# Atmega328.net
KiCad netlist of a schematic drawn in Altium Designer
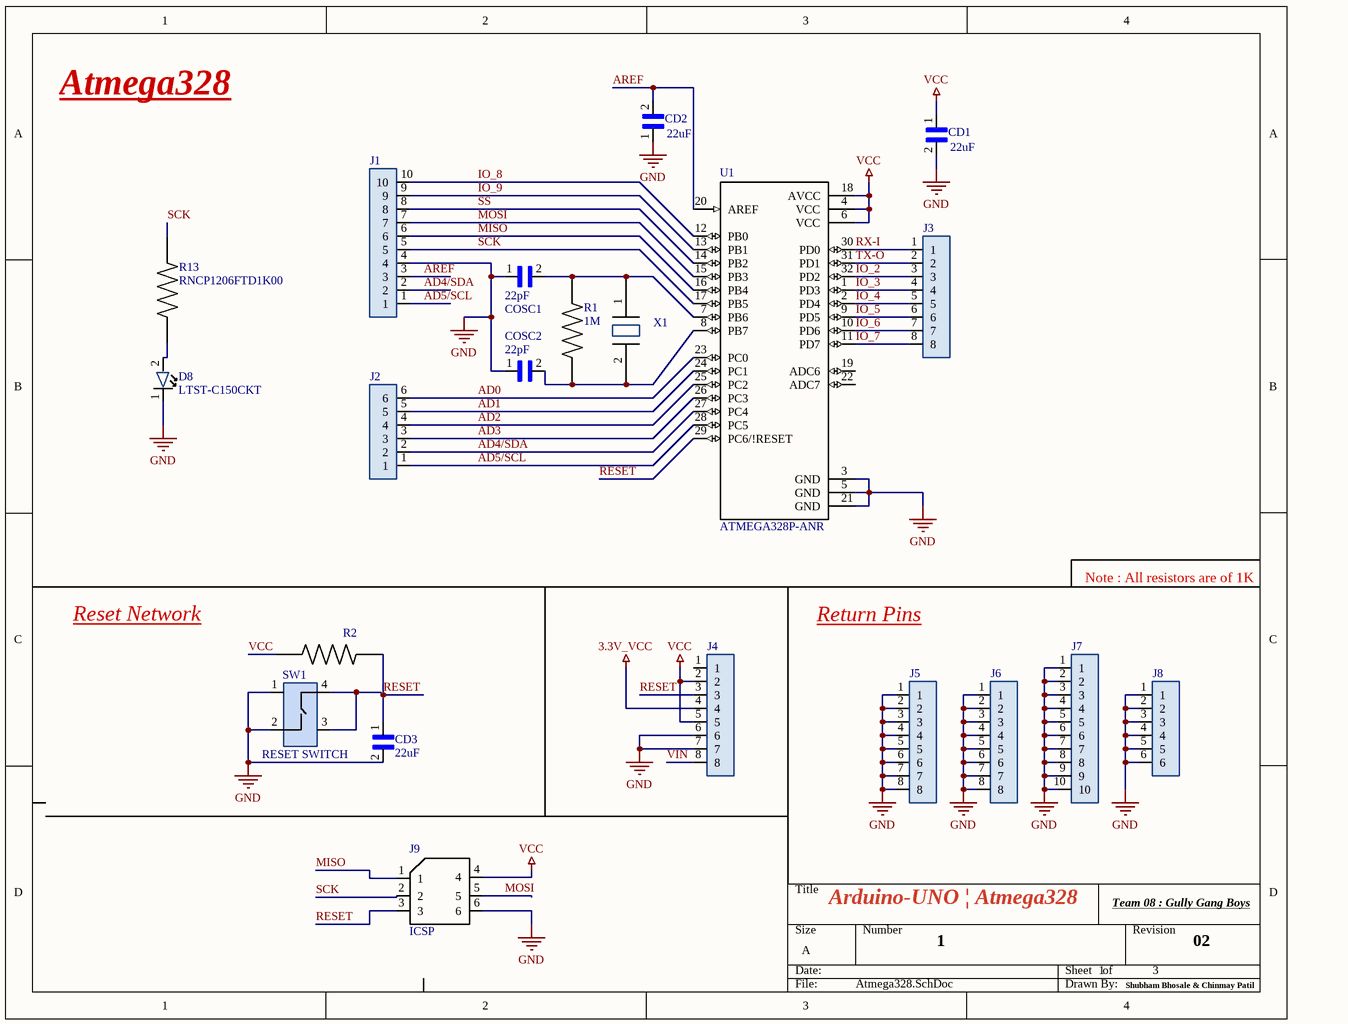
[diagram p0: Atmega328.SchDoc]

(export (version "E")
  (design (tool "Eeschema 10.0.6"))
  (components
    (comp (ref "CD1")
      (value "22uF")
      (footprint "1206_Passive")
      (description "22µF ±20% 16V Ceramic Capacitor X5R 1206 (3216 Metric)")
      (fields (field (name "DIGIKEY PART") "1276-2728-1-ND"))
      (libsource (lib "brd2_rev2") (part "1206_22uF"))
    )
    (comp (ref "CD2")
      (value "22uF")
      (footprint "1206_Passive")
      (description "22µF ±20% 16V Ceramic Capacitor X5R 1206 (3216 Metric)")
      (fields (field (name "DIGIKEY PART") "1276-2728-1-ND"))
      (libsource (lib "brd2_rev2") (part "1206_22uF"))
    )
    (comp (ref "CD3")
      (value "22uF")
      (footprint "1206_Passive")
      (description "22µF ±20% 16V Ceramic Capacitor X5R 1206 (3216 Metric)")
      (fields (field (name "DIGIKEY PART") "1276-2728-1-ND"))
      (libsource (lib "brd2_rev2") (part "1206_22uF"))
    )
    (comp (ref "COSC1")
      (value "22pF")
      (footprint "1206_Passive")
      (description "22pF ±5% 16V Ceramic Capacitor C0G, NP0 1206 (3216 Metric)")
      (fields (field (name "DIGIKEY PART") "732-7867-1-ND"))
      (libsource (lib "brd2_rev2") (part "1206_22pF"))
    )
    (comp (ref "COSC2")
      (value "22pF")
      (footprint "1206_Passive")
      (description "22pF ±5% 16V Ceramic Capacitor C0G, NP0 1206 (3216 Metric)")
      (fields (field (name "DIGIKEY PART") "732-7867-1-ND"))
      (libsource (lib "brd2_rev2") (part "1206_22pF"))
    )
    (comp (ref "D8")
      (value "LTST-C150CKT")
      (footprint "LED")
      (description "Red 638nm LED Indication - Discrete 1.8V 1206 (3216 Metric)")
      (fields (field (name "DIGIKEY PART") "160-1167-1-ND"))
      (libsource (lib "brd2_rev2") (part "1206_RED_LED"))
    )
    (comp (ref "J1")
      (value "PPTC101LFBN-RC")
      (footprint "10_PIN")
      (description "10 Position Header Connector 0.100\" (2.54mm) Through Hole Tin")
      (fields (field (name "DIGIKEY PART") "S7008-ND"))
      (libsource (lib "") (part "10_PIN_FEMALE_1"))
    )
    (comp (ref "J2")
      (value "PPTC061LFBN-RC")
      (footprint "6_PIN")
      (description "6 Position Header Connector 0.100\" (2.54mm) Through Hole Tin")
      (fields (field (name "DIGIKEY PART") "S7004-ND"))
      (libsource (lib "brd2_rev2") (part "6_PIN_FEMALE"))
    )
    (comp (ref "J3")
      (value "PPTC081LFBN-RC")
      (footprint "8_PIN")
      (description "8 Position Header Connector 0.100\" (2.54mm) Through Hole Tin")
      (fields (field (name "DIGIKEY PART") "S7006-ND"))
      (libsource (lib "brd2_rev2") (part "8_PIN_FEMALE"))
    )
    (comp (ref "J4")
      (value "PPTC081LFBN-RC")
      (footprint "8_PIN")
      (description "8 Position Header Connector 0.100\" (2.54mm) Through Hole Tin")
      (fields (field (name "DIGIKEY PART") "S7006-ND"))
      (libsource (lib "brd2_rev2") (part "8_PIN_FEMALE"))
    )
    (comp (ref "J5")
      (value "PPTC081LFBN-RC")
      (footprint "8_PIN")
      (description "8 Position Header Connector 0.100\" (2.54mm) Through Hole Tin")
      (fields (field (name "DIGIKEY PART") "S7006-ND"))
      (libsource (lib "brd2_rev2") (part "8_PIN_FEMALE"))
    )
    (comp (ref "J6")
      (value "PPTC081LFBN-RC")
      (footprint "8_PIN")
      (description "8 Position Header Connector 0.100\" (2.54mm) Through Hole Tin")
      (fields (field (name "DIGIKEY PART") "S7006-ND"))
      (libsource (lib "brd2_rev2") (part "8_PIN_FEMALE"))
    )
    (comp (ref "J7")
      (value "PPTC101LFBN-RC")
      (footprint "10_PIN")
      (description "10 Position Header Connector 0.100\" (2.54mm) Through Hole Tin")
      (fields (field (name "DIGIKEY PART") "S7008-ND"))
      (libsource (lib "brd2_rev2") (part "10_PIN_FEMALE"))
    )
    (comp (ref "J8")
      (value "PPTC061LFBN-RC")
      (footprint "6_PIN")
      (description "6 Position Header Connector 0.100\" (2.54mm) Through Hole Tin")
      (fields (field (name "DIGIKEY PART") "S7004-ND"))
      (libsource (lib "") (part "6_PIN_FEMALE_1"))
    )
    (comp (ref "J9")
      (value "ICSP")
      (footprint "ICSP")
      (description "Connector Header Through Hole 6 position 0.079\" (2.00mm)")
      (fields (field (name "DIGIKEY PART") "S5801-03-ND"))
      (libsource (lib "brd2_rev2") (part "ICSP"))
    )
    (comp (ref "R1")
      (value "1M")
      (footprint "1206_Passive")
      (description "1 MOhms ±5% 0.25W, 1/4W Chip Resistor 1206 (3216 Metric) Automotive AEC-Q200 Thick Film")
      (fields (field (name "DIGIKEY PART") "Number RMCF1206JT1M00CT-ND"))
      (libsource (lib "brd2_rev2") (part "1206_1M"))
    )
    (comp (ref "R2")
      (value "RNCP1206FTD1K00")
      (footprint "1206_Passive")
      (description "1 kOhms ±1% 0.5W, 1/2W Chip Resistor 1206 (3216 Metric) Anti-Sulfur, Moisture Resistant Thin Film")
      (fields (field (name "DIGIKEY PART") "RNCP1206FTD1K00CT-ND"))
      (libsource (lib "brd2_rev2") (part "1206_1K"))
    )
    (comp (ref "R13")
      (value "RNCP1206FTD1K00")
      (footprint "1206_Passive")
      (description "1 kOhms ±1% 0.5W, 1/2W Chip Resistor 1206 (3216 Metric) Anti-Sulfur, Moisture Resistant Thin Film")
      (fields (field (name "DIGIKEY PART") "RNCP1206FTD1K00CT-ND"))
      (libsource (lib "brd2_rev2") (part "1206_1K"))
    )
    (comp (ref "SW1")
      (value "RESET SWITCH")
      (footprint "Switch")
      (description "Tactile Switch SPST-NO Top Actuated Surface Mount")
      (fields (field (name "DIGIKEY PART") "EG5350CT-ND"))
      (libsource (lib "brd2_rev2") (part "Push_Button"))
    )
    (comp (ref "U1")
      (value "ATMEGA328P-ANR")
      (footprint "ATMega328P")
      (description "AVR AVR® ATmega Microcontroller IC 8-Bit 20MHz 32KB (16K x 16) FLASH 32-TQFP (7x7)")
      (fields (field (name "DIGIKEY PART") "ATMEGA328P-ANRCT-ND"))
      (libsource (lib "brd2_rev2") (part "ATMega328P"))
    )
    (comp (ref "X1")
      (value "ABLS-16.000MHZ-B4-T")
      (footprint "Crystal")
      (description "16MHz ±30ppm Crystal 18pF 40 Ohms HC-49/US")
      (fields (field (name "DIGIKEY PART") "535-10226-1-ND"))
      (libsource (lib "brd2_rev2") (part "16MHz_Crystal"))
    )
  )
  (nets
    (net (code "1") (name "/AD0") (class "Default")
      (node (ref "J2") (pin "6") (pinfunction "6_6") (pintype "passive"))
      (node (ref "U1") (pin "23") (pinfunction "PC0_23") (pintype "bidirectional"))
    )
    (net (code "2") (name "/AD1") (class "Default")
      (node (ref "J2") (pin "5") (pinfunction "5_5") (pintype "passive"))
      (node (ref "U1") (pin "24") (pinfunction "PC1_24") (pintype "bidirectional"))
    )
    (net (code "3") (name "/AD2") (class "Default")
      (node (ref "J2") (pin "4") (pinfunction "4_4") (pintype "passive"))
      (node (ref "U1") (pin "25") (pinfunction "PC2_25") (pintype "bidirectional"))
    )
    (net (code "4") (name "/AD3") (class "Default")
      (node (ref "J2") (pin "3") (pinfunction "3_3") (pintype "passive"))
      (node (ref "U1") (pin "26") (pinfunction "PC3_26") (pintype "bidirectional"))
    )
    (net (code "5") (name "/AD4{slash}SDA") (class "Default")
      (node (ref "J1") (pin "2") (pinfunction "2_2") (pintype "passive"))
      (node (ref "J2") (pin "2") (pinfunction "2_2") (pintype "passive"))
      (node (ref "U1") (pin "27") (pinfunction "PC4_27") (pintype "bidirectional"))
    )
    (net (code "6") (name "/AD5{slash}SCL") (class "Default")
      (node (ref "J1") (pin "1") (pinfunction "1_1") (pintype "passive"))
      (node (ref "J2") (pin "1") (pinfunction "1_1") (pintype "passive"))
      (node (ref "U1") (pin "28") (pinfunction "PC5_28") (pintype "bidirectional"))
    )
    (net (code "7") (name "/AREF") (class "Default")
      (node (ref "CD2") (pin "2") (pinfunction "2_2") (pintype "passive"))
      (node (ref "J1") (pin "3") (pinfunction "3_3") (pintype "passive"))
      (node (ref "U1") (pin "20") (pinfunction "AREF_20") (pintype "input"))
    )
    (net (code "8") (name "/IO_2") (class "Default")
      (node (ref "J3") (pin "3") (pinfunction "3_3") (pintype "passive"))
      (node (ref "U1") (pin "32") (pinfunction "PD2_32") (pintype "bidirectional"))
    )
    (net (code "9") (name "/IO_3") (class "Default")
      (node (ref "J3") (pin "4") (pinfunction "4_4") (pintype "passive"))
      (node (ref "U1") (pin "1") (pinfunction "PD3_1") (pintype "bidirectional"))
    )
    (net (code "10") (name "/IO_4") (class "Default")
      (node (ref "J3") (pin "5") (pinfunction "5_5") (pintype "passive"))
      (node (ref "U1") (pin "2") (pinfunction "PD4_2") (pintype "bidirectional"))
    )
    (net (code "11") (name "/IO_5") (class "Default")
      (node (ref "J3") (pin "6") (pinfunction "6_6") (pintype "passive"))
      (node (ref "U1") (pin "9") (pinfunction "PD5_9") (pintype "bidirectional"))
    )
    (net (code "12") (name "/IO_6") (class "Default")
      (node (ref "J3") (pin "7") (pinfunction "7_7") (pintype "passive"))
      (node (ref "U1") (pin "10") (pinfunction "PD6_10") (pintype "bidirectional"))
    )
    (net (code "13") (name "/IO_7") (class "Default")
      (node (ref "J3") (pin "8") (pinfunction "8_8") (pintype "passive"))
      (node (ref "U1") (pin "11") (pinfunction "PD7_11") (pintype "bidirectional"))
    )
    (net (code "14") (name "/IO_8") (class "Default")
      (node (ref "J1") (pin "10") (pinfunction "10_10") (pintype "passive"))
      (node (ref "U1") (pin "12") (pinfunction "PB0_12") (pintype "bidirectional"))
    )
    (net (code "15") (name "/IO_9") (class "Default")
      (node (ref "J1") (pin "9") (pinfunction "9_9") (pintype "passive"))
      (node (ref "U1") (pin "13") (pinfunction "PB1_13") (pintype "bidirectional"))
    )
    (net (code "16") (name "/MISO") (class "Default")
      (node (ref "J1") (pin "6") (pinfunction "6_6") (pintype "passive"))
      (node (ref "J9") (pin "1") (pinfunction "1_1") (pintype "passive"))
      (node (ref "U1") (pin "16") (pinfunction "PB4_16") (pintype "bidirectional"))
    )
    (net (code "17") (name "/MOSI") (class "Default")
      (node (ref "J1") (pin "7") (pinfunction "7_7") (pintype "passive"))
      (node (ref "J9") (pin "5") (pinfunction "5_5") (pintype "passive"))
      (node (ref "U1") (pin "15") (pinfunction "PB3_15") (pintype "bidirectional"))
    )
    (net (code "18") (name "/RESET") (class "Default")
      (node (ref "CD3") (pin "1") (pinfunction "1_1") (pintype "passive"))
      (node (ref "J4") (pin "3") (pinfunction "3_3") (pintype "passive"))
      (node (ref "J9") (pin "3") (pinfunction "3_3") (pintype "passive"))
      (node (ref "R2") (pin "2") (pinfunction "2_2") (pintype "passive"))
      (node (ref "SW1") (pin "3") (pinfunction "3_3") (pintype "passive"))
      (node (ref "SW1") (pin "4") (pinfunction "4_4") (pintype "passive"))
      (node (ref "U1") (pin "29") (pinfunction "PC6/!RESET_29") (pintype "bidirectional"))
    )
    (net (code "19") (name "/RX-I") (class "Default")
      (node (ref "J3") (pin "1") (pinfunction "1_1") (pintype "passive"))
      (node (ref "U1") (pin "30") (pinfunction "PD0_30") (pintype "bidirectional"))
    )
    (net (code "20") (name "/SCK") (class "Default")
      (node (ref "J1") (pin "5") (pinfunction "5_5") (pintype "passive"))
      (node (ref "J9") (pin "2") (pinfunction "2_2") (pintype "passive"))
      (node (ref "R13") (pin "2") (pinfunction "2_2") (pintype "passive"))
      (node (ref "U1") (pin "17") (pinfunction "PB5_17") (pintype "bidirectional"))
    )
    (net (code "21") (name "/SS") (class "Default")
      (node (ref "J1") (pin "8") (pinfunction "8_8") (pintype "passive"))
      (node (ref "U1") (pin "14") (pinfunction "PB2_14") (pintype "bidirectional"))
    )
    (net (code "22") (name "/TX-O") (class "Default")
      (node (ref "J3") (pin "2") (pinfunction "2_2") (pintype "passive"))
      (node (ref "U1") (pin "31") (pinfunction "PD1_31") (pintype "bidirectional"))
    )
    (net (code "23") (name "/VIN") (class "Default")
      (node (ref "J4") (pin "8") (pinfunction "8_8") (pintype "passive"))
    )
    (net (code "24") (name "3.3V_VCC") (class "Default")
      (node (ref "J4") (pin "4") (pinfunction "4_4") (pintype "passive"))
    )
    (net (code "25") (name "GND") (class "Default")
      (node (ref "CD1") (pin "2") (pinfunction "2_2") (pintype "passive"))
      (node (ref "CD2") (pin "1") (pinfunction "1_1") (pintype "passive"))
      (node (ref "CD3") (pin "2") (pinfunction "2_2") (pintype "passive"))
      (node (ref "COSC1") (pin "1") (pinfunction "1_1") (pintype "passive"))
      (node (ref "COSC2") (pin "1") (pinfunction "1_1") (pintype "passive"))
      (node (ref "D8") (pin "1") (pinfunction "1_1") (pintype "passive"))
      (node (ref "J1") (pin "4") (pinfunction "4_4") (pintype "passive"))
      (node (ref "J4") (pin "6") (pinfunction "6_6") (pintype "passive"))
      (node (ref "J4") (pin "7") (pinfunction "7_7") (pintype "passive"))
      (node (ref "J5") (pin "1") (pinfunction "1_1") (pintype "passive"))
      (node (ref "J5") (pin "2") (pinfunction "2_2") (pintype "passive"))
      (node (ref "J5") (pin "3") (pinfunction "3_3") (pintype "passive"))
      (node (ref "J5") (pin "4") (pinfunction "4_4") (pintype "passive"))
      (node (ref "J5") (pin "5") (pinfunction "5_5") (pintype "passive"))
      (node (ref "J5") (pin "6") (pinfunction "6_6") (pintype "passive"))
      (node (ref "J5") (pin "7") (pinfunction "7_7") (pintype "passive"))
      (node (ref "J5") (pin "8") (pinfunction "8_8") (pintype "passive"))
      (node (ref "J6") (pin "1") (pinfunction "1_1") (pintype "passive"))
      (node (ref "J6") (pin "2") (pinfunction "2_2") (pintype "passive"))
      (node (ref "J6") (pin "3") (pinfunction "3_3") (pintype "passive"))
      (node (ref "J6") (pin "4") (pinfunction "4_4") (pintype "passive"))
      (node (ref "J6") (pin "5") (pinfunction "5_5") (pintype "passive"))
      (node (ref "J6") (pin "6") (pinfunction "6_6") (pintype "passive"))
      (node (ref "J6") (pin "7") (pinfunction "7_7") (pintype "passive"))
      (node (ref "J6") (pin "8") (pinfunction "8_8") (pintype "passive"))
      (node (ref "J7") (pin "1") (pinfunction "1_1") (pintype "passive"))
      (node (ref "J7") (pin "10") (pinfunction "10_10") (pintype "passive"))
      (node (ref "J7") (pin "2") (pinfunction "2_2") (pintype "passive"))
      (node (ref "J7") (pin "3") (pinfunction "3_3") (pintype "passive"))
      (node (ref "J7") (pin "4") (pinfunction "4_4") (pintype "passive"))
      (node (ref "J7") (pin "5") (pinfunction "5_5") (pintype "passive"))
      (node (ref "J7") (pin "6") (pinfunction "6_6") (pintype "passive"))
      (node (ref "J7") (pin "7") (pinfunction "7_7") (pintype "passive"))
      (node (ref "J7") (pin "8") (pinfunction "8_8") (pintype "passive"))
      (node (ref "J7") (pin "9") (pinfunction "9_9") (pintype "passive"))
      (node (ref "J8") (pin "1") (pinfunction "1_1") (pintype "passive"))
      (node (ref "J8") (pin "2") (pinfunction "2_2") (pintype "passive"))
      (node (ref "J8") (pin "3") (pinfunction "3_3") (pintype "passive"))
      (node (ref "J8") (pin "4") (pinfunction "4_4") (pintype "passive"))
      (node (ref "J8") (pin "5") (pinfunction "5_5") (pintype "passive"))
      (node (ref "J8") (pin "6") (pinfunction "6_6") (pintype "passive"))
      (node (ref "J9") (pin "6") (pinfunction "6_6") (pintype "passive"))
      (node (ref "SW1") (pin "1") (pinfunction "1_1") (pintype "passive"))
      (node (ref "SW1") (pin "2") (pinfunction "2_2") (pintype "passive"))
      (node (ref "U1") (pin "21") (pinfunction "GND_21") (pintype "power_in"))
      (node (ref "U1") (pin "3") (pinfunction "GND_3") (pintype "power_in"))
      (node (ref "U1") (pin "5") (pinfunction "GND_5") (pintype "power_in"))
    )
    (net (code "26") (name "Net-(D8-Pad2)") (class "Default")
      (node (ref "D8") (pin "2") (pinfunction "2_2") (pintype "passive"))
      (node (ref "R13") (pin "1") (pinfunction "1_1") (pintype "passive"))
    )
    (net (code "27") (name "Net-(U1-PB6)") (class "Default")
      (node (ref "COSC1") (pin "2") (pinfunction "2_2") (pintype "passive"))
      (node (ref "R1") (pin "2") (pinfunction "2_2") (pintype "passive"))
      (node (ref "U1") (pin "7") (pinfunction "PB6_7") (pintype "bidirectional"))
      (node (ref "X1") (pin "1") (pinfunction "1_1") (pintype "passive"))
    )
    (net (code "28") (name "Net-(U1-PB7)") (class "Default")
      (node (ref "COSC2") (pin "2") (pinfunction "2_2") (pintype "passive"))
      (node (ref "R1") (pin "1") (pinfunction "1_1") (pintype "passive"))
      (node (ref "U1") (pin "8") (pinfunction "PB7_8") (pintype "bidirectional"))
      (node (ref "X1") (pin "2") (pinfunction "2_2") (pintype "passive"))
    )
    (net (code "29") (name "VCC") (class "Default")
      (node (ref "CD1") (pin "1") (pinfunction "1_1") (pintype "passive"))
      (node (ref "J4") (pin "2") (pinfunction "2_2") (pintype "passive"))
      (node (ref "J4") (pin "5") (pinfunction "5_5") (pintype "passive"))
      (node (ref "J9") (pin "4") (pinfunction "4_4") (pintype "passive"))
      (node (ref "R2") (pin "1") (pinfunction "1_1") (pintype "passive"))
      (node (ref "U1") (pin "18") (pinfunction "AVCC_18") (pintype "power_in"))
      (node (ref "U1") (pin "4") (pinfunction "VCC_4") (pintype "power_in"))
      (node (ref "U1") (pin "6") (pinfunction "VCC_6") (pintype "power_in"))
    )
    (net (code "30") (name "unconnected-(J4-Pad1)") (class "Default")
      (node (ref "J4") (pin "1") (pinfunction "1_1") (pintype "passive"))
    )
    (net (code "31") (name "unconnected-(U1-ADC6-Pad19)") (class "Default")
      (node (ref "U1") (pin "19") (pinfunction "ADC6_19") (pintype "bidirectional"))
    )
    (net (code "32") (name "unconnected-(U1-ADC7-Pad22)") (class "Default")
      (node (ref "U1") (pin "22") (pinfunction "ADC7_22") (pintype "bidirectional"))
    )
  )
)
